# ProPrj__1__2024-10-14.net
KiCad netlist of a schematic drawn in EasyEDA Pro
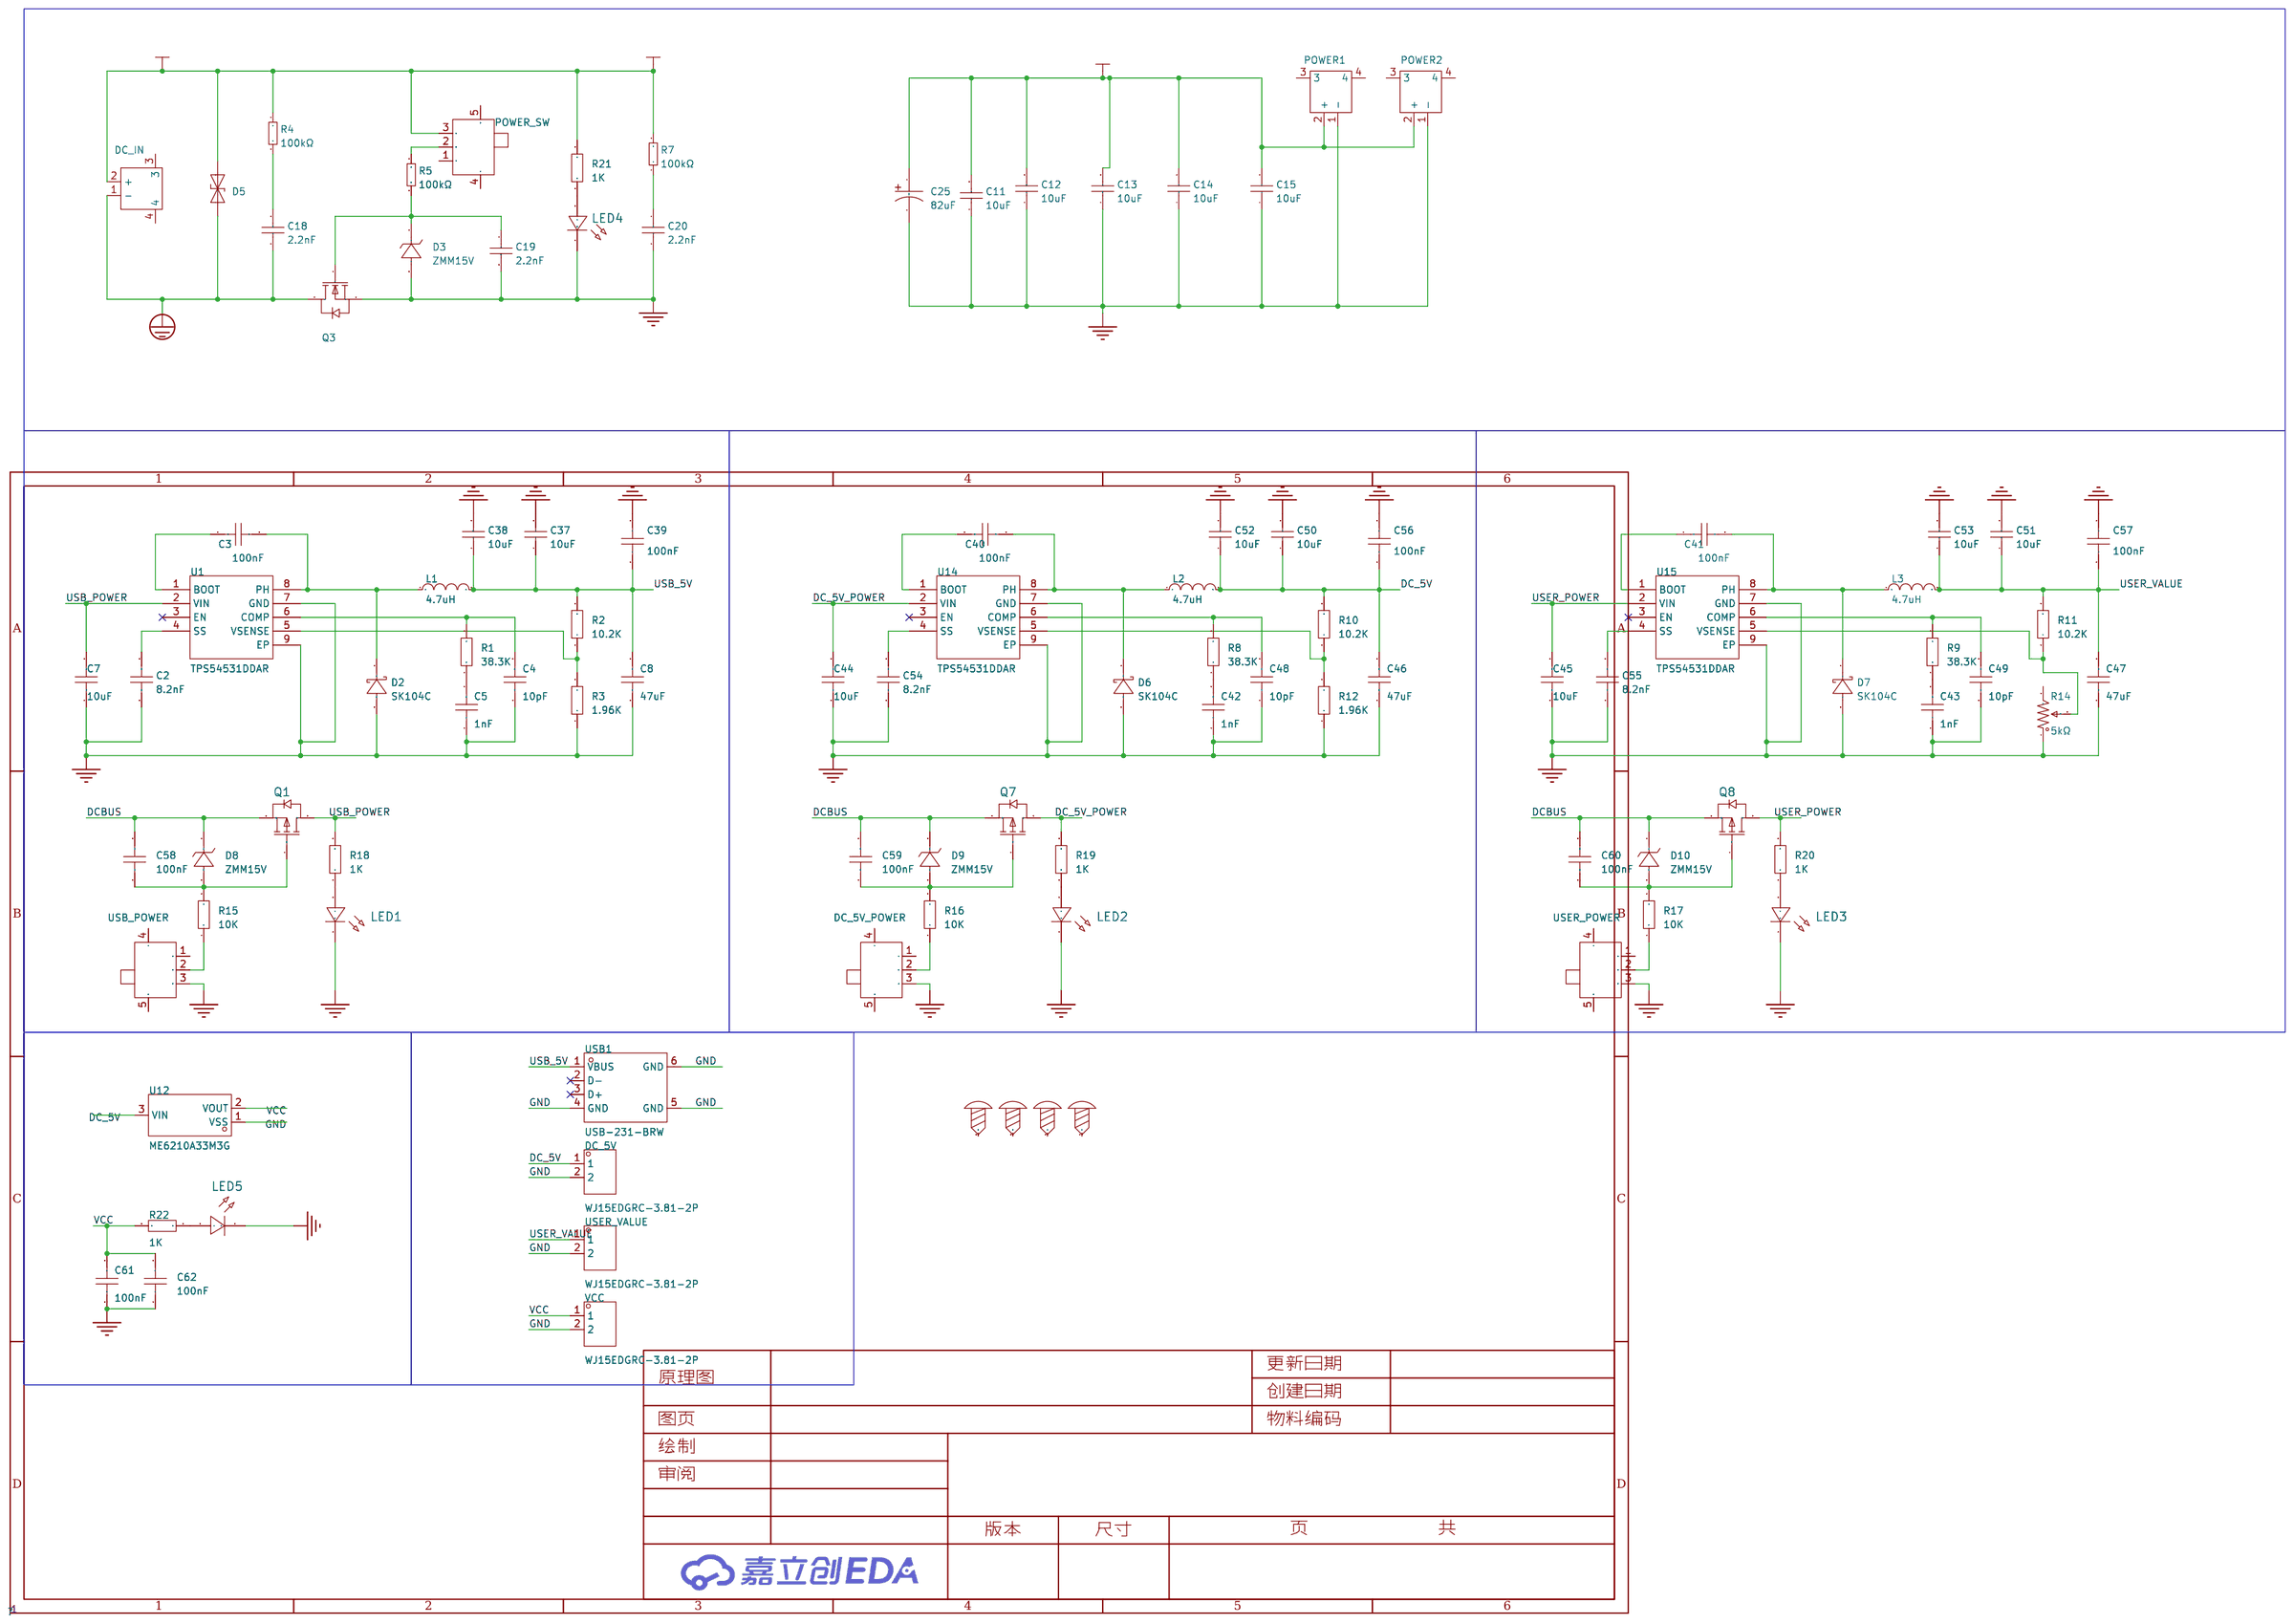
[diagram p0: schematic sheet]

(export (version "E")
  (design (tool "Eeschema 10.0.6"))
  (components
    (comp (ref "C2")
      (value "8.2nF")
      (footprint "easyedapro:C0603")
      (libsource (lib "easyedapro") (part "CapAcitance"))
    )
    (comp (ref "C3")
      (value "100nF")
      (footprint "easyedapro:C0603")
      (libsource (lib "easyedapro") (part "CapAcitance"))
    )
    (comp (ref "C4")
      (value "10pF")
      (footprint "easyedapro:C0603")
      (libsource (lib "easyedapro") (part "CapAcitance"))
    )
    (comp (ref "C5")
      (value "1nF")
      (footprint "easyedapro:C0603")
      (libsource (lib "easyedapro") (part "CapAcitance"))
    )
    (comp (ref "C7")
      (value "10uF")
      (footprint "easyedapro:C1210")
      (description "容值:10uF;精度:±10%;额定电压:50V;材质(温度系数):X7R;")
      (fields
        (field (name "Manufacturer Part") "CL32B106KBJNNNE")
        (field (name "Manufacturer") "SAMSUNG(三星)")
      )
      (libsource (lib "easyedapro") (part "CL32B106KBJNNNE"))
    )
    (comp (ref "C8")
      (value "47uF")
      (footprint "easyedapro:C1210")
      (description "容值:47uF;精度:±10%;额定电压:16V;材质(温度系数):X5R;")
      (fields
        (field (name "Manufacturer Part") "CC1210KKX5R7BB476")
        (field (name "Manufacturer") "YAGEO(国巨)")
      )
      (libsource (lib "easyedapro") (part "CC1210KKX5R7BB476"))
    )
    (comp (ref "C11") (value "10uF") (footprint "easyedapro:C1206_S") (libsource (lib "") (part "C1206_S_1")))
    (comp (ref "C12") (value "10uF") (footprint "easyedapro:C1206_S") (libsource (lib "") (part "C1206_S_1")))
    (comp (ref "C13") (value "10uF") (footprint "easyedapro:C1206_S") (libsource (lib "") (part "C1206_S_1")))
    (comp (ref "C14") (value "10uF") (footprint "easyedapro:C1206_S") (libsource (lib "") (part "C1206_S_1")))
    (comp (ref "C15") (value "10uF") (footprint "easyedapro:C1206_S") (libsource (lib "") (part "C1206_S_1")))
    (comp (ref "C18")
      (value "2.2nF")
      (footprint "easyedapro:C0603_S")
      (fields (field (name "Manufacturer Part") "0603B222K500NT") (field (name "Manufacturer") "FH(风华)"))
      (libsource (lib "easyedapro") (part "C0603_S"))
    )
    (comp (ref "C19")
      (value "2.2nF")
      (footprint "easyedapro:C0603_S")
      (fields (field (name "Manufacturer Part") "0603B222K500NT") (field (name "Manufacturer") "FH(风华)"))
      (libsource (lib "easyedapro") (part "C0603_S"))
    )
    (comp (ref "C20")
      (value "2.2nF")
      (footprint "easyedapro:C0603_S")
      (fields (field (name "Manufacturer Part") "0603B222K500NT") (field (name "Manufacturer") "FH(风华)"))
      (libsource (lib "easyedapro") (part "C0603_S"))
    )
    (comp (ref "C25")
      (value "82uF")
      (footprint "easyedapro:CAP-SMD_BD10.0-L10.3-W10.3-LS11.0-R-RD")
      (description "容值:82uF;精度:±20%;额定电压:80V;纹波电流:668mA@100kHz;等效串联电阻:-;")
      (fields (field (name "Manufacturer Part") "VKME1001K820MV") (field (name "Manufacturer") "Ymin(永铭)"))
      (libsource (lib "easyedapro") (part "VKME1001K820MV"))
    )
    (comp (ref "C37")
      (value "10uF")
      (footprint "easyedapro:C1206_S")
      (libsource (lib "easyedapro") (part "C1206_S"))
    )
    (comp (ref "C38")
      (value "10uF")
      (footprint "easyedapro:C1206_S")
      (libsource (lib "easyedapro") (part "C1206_S"))
    )
    (comp (ref "C39")
      (value "100nF")
      (footprint "easyedapro:C0603")
      (libsource (lib "easyedapro") (part "CapAcitance"))
    )
    (comp (ref "C40")
      (value "100nF")
      (footprint "easyedapro:C0603")
      (libsource (lib "easyedapro") (part "CapAcitance"))
    )
    (comp (ref "C41")
      (value "100nF")
      (footprint "easyedapro:C0603")
      (libsource (lib "easyedapro") (part "CapAcitance"))
    )
    (comp (ref "C42")
      (value "1nF")
      (footprint "easyedapro:C0603")
      (libsource (lib "easyedapro") (part "CapAcitance"))
    )
    (comp (ref "C43")
      (value "1nF")
      (footprint "easyedapro:C0603")
      (libsource (lib "easyedapro") (part "CapAcitance"))
    )
    (comp (ref "C44")
      (value "10uF")
      (footprint "easyedapro:C1210")
      (description "容值:10uF;精度:±10%;额定电压:50V;材质(温度系数):X7R;")
      (fields
        (field (name "Manufacturer Part") "CL32B106KBJNNNE")
        (field (name "Manufacturer") "SAMSUNG(三星)")
      )
      (libsource (lib "easyedapro") (part "CL32B106KBJNNNE"))
    )
    (comp (ref "C45")
      (value "10uF")
      (footprint "easyedapro:C1210")
      (description "容值:10uF;精度:±10%;额定电压:50V;材质(温度系数):X7R;")
      (fields
        (field (name "Manufacturer Part") "CL32B106KBJNNNE")
        (field (name "Manufacturer") "SAMSUNG(三星)")
      )
      (libsource (lib "easyedapro") (part "CL32B106KBJNNNE"))
    )
    (comp (ref "C46")
      (value "47uF")
      (footprint "easyedapro:C1210")
      (description "容值:47uF;精度:±10%;额定电压:16V;材质(温度系数):X5R;")
      (fields
        (field (name "Manufacturer Part") "CC1210KKX5R7BB476")
        (field (name "Manufacturer") "YAGEO(国巨)")
      )
      (libsource (lib "easyedapro") (part "CC1210KKX5R7BB476"))
    )
    (comp (ref "C47")
      (value "47uF")
      (footprint "easyedapro:C1210")
      (description "容值:47uF;精度:±10%;额定电压:16V;材质(温度系数):X5R;")
      (fields
        (field (name "Manufacturer Part") "CC1210KKX5R7BB476")
        (field (name "Manufacturer") "YAGEO(国巨)")
      )
      (libsource (lib "easyedapro") (part "CC1210KKX5R7BB476"))
    )
    (comp (ref "C48")
      (value "10pF")
      (footprint "easyedapro:C0603")
      (libsource (lib "easyedapro") (part "CapAcitance"))
    )
    (comp (ref "C49")
      (value "10pF")
      (footprint "easyedapro:C0603")
      (libsource (lib "easyedapro") (part "CapAcitance"))
    )
    (comp (ref "C50")
      (value "10uF")
      (footprint "easyedapro:C1206_S")
      (libsource (lib "easyedapro") (part "C1206_S"))
    )
    (comp (ref "C51")
      (value "10uF")
      (footprint "easyedapro:C1206_S")
      (libsource (lib "easyedapro") (part "C1206_S"))
    )
    (comp (ref "C52")
      (value "10uF")
      (footprint "easyedapro:C1206_S")
      (libsource (lib "easyedapro") (part "C1206_S"))
    )
    (comp (ref "C53")
      (value "10uF")
      (footprint "easyedapro:C1206_S")
      (libsource (lib "easyedapro") (part "C1206_S"))
    )
    (comp (ref "C54")
      (value "8.2nF")
      (footprint "easyedapro:C0603")
      (libsource (lib "easyedapro") (part "CapAcitance"))
    )
    (comp (ref "C55")
      (value "8.2nF")
      (footprint "easyedapro:C0603")
      (libsource (lib "easyedapro") (part "CapAcitance"))
    )
    (comp (ref "C56")
      (value "100nF")
      (footprint "easyedapro:C0603")
      (libsource (lib "easyedapro") (part "CapAcitance"))
    )
    (comp (ref "C57")
      (value "100nF")
      (footprint "easyedapro:C0603")
      (libsource (lib "easyedapro") (part "CapAcitance"))
    )
    (comp (ref "C58")
      (value "100nF")
      (footprint "easyedapro:C0603")
      (libsource (lib "easyedapro") (part "CapAcitance"))
    )
    (comp (ref "C59")
      (value "100nF")
      (footprint "easyedapro:C0603")
      (libsource (lib "easyedapro") (part "CapAcitance"))
    )
    (comp (ref "C60")
      (value "100nF")
      (footprint "easyedapro:C0603")
      (libsource (lib "easyedapro") (part "CapAcitance"))
    )
    (comp (ref "C61")
      (value "100nF")
      (footprint "easyedapro:C0603")
      (libsource (lib "easyedapro") (part "CapAcitance"))
    )
    (comp (ref "C62")
      (value "100nF")
      (footprint "easyedapro:C0603")
      (libsource (lib "easyedapro") (part "CapAcitance"))
    )
    (comp (ref "D2")
      (value "SK104C")
      (footprint "easyedapro:SMC_L6.9-W5.9-LS7.9-RD")
      (description "二极管配置:独立式;正向压降(Vf):550mV@10A;直流反向耐压(Vr):40V;平均整流电流(Io):10A;")
      (fields (field (name "Manufacturer") "宏迦橙"))
      (libsource (lib "easyedapro") (part "SK104C"))
    )
    (comp (ref "D3")
      (value "ZMM15V")
      (footprint "easyedapro:LL-34_L3.5-W1.5-RD-2")
      (description "二极管配置:独立式;稳压值(标称值):15V;稳压值(范围):13.8V~15.6V;精度:±5%;功率:500mW;阻抗(Zzt):30Ω;")
      (fields (field (name "Manufacturer") "YONGYUTAI(永裕泰)"))
      (libsource (lib "easyedapro") (part "ZMM15V"))
    )
    (comp (ref "D5")
      (value "1.5SMC30CAHE3/57T")
      (footprint "easyedapro:SMC_L6.8-W5.9-LS7.8-BI")
      (fields (field (name "Manufacturer") "VISHAY(威世)"))
      (libsource (lib "easyedapro") (part "1.5SMC30CAHE3/57T"))
    )
    (comp (ref "D6")
      (value "SK104C")
      (footprint "easyedapro:SMC_L6.9-W5.9-LS7.9-RD")
      (description "二极管配置:独立式;正向压降(Vf):550mV@10A;直流反向耐压(Vr):40V;平均整流电流(Io):10A;")
      (fields (field (name "Manufacturer") "宏迦橙"))
      (libsource (lib "easyedapro") (part "SK104C"))
    )
    (comp (ref "D7")
      (value "SK104C")
      (footprint "easyedapro:SMC_L6.9-W5.9-LS7.9-RD")
      (description "二极管配置:独立式;正向压降(Vf):550mV@10A;直流反向耐压(Vr):40V;平均整流电流(Io):10A;")
      (fields (field (name "Manufacturer") "宏迦橙"))
      (libsource (lib "easyedapro") (part "SK104C"))
    )
    (comp (ref "D8")
      (value "ZMM15V")
      (footprint "easyedapro:LL-34_L3.5-W1.5-RD-2")
      (description "二极管配置:独立式;稳压值(标称值):15V;稳压值(范围):13.8V~15.6V;精度:±5%;功率:500mW;阻抗(Zzt):30Ω;")
      (fields (field (name "Manufacturer") "YONGYUTAI(永裕泰)"))
      (libsource (lib "easyedapro") (part "ZMM15V"))
    )
    (comp (ref "D9")
      (value "ZMM15V")
      (footprint "easyedapro:LL-34_L3.5-W1.5-RD-2")
      (description "二极管配置:独立式;稳压值(标称值):15V;稳压值(范围):13.8V~15.6V;精度:±5%;功率:500mW;阻抗(Zzt):30Ω;")
      (fields (field (name "Manufacturer") "YONGYUTAI(永裕泰)"))
      (libsource (lib "easyedapro") (part "ZMM15V"))
    )
    (comp (ref "D10")
      (value "ZMM15V")
      (footprint "easyedapro:LL-34_L3.5-W1.5-RD-2")
      (description "二极管配置:独立式;稳压值(标称值):15V;稳压值(范围):13.8V~15.6V;精度:±5%;功率:500mW;阻抗(Zzt):30Ω;")
      (fields (field (name "Manufacturer") "YONGYUTAI(永裕泰)"))
      (libsource (lib "easyedapro") (part "ZMM15V"))
    )
    (comp (ref "DC_5V")
      (value "WJ15EDGRC-3.81-2P")
      (footprint "easyedapro:CONN-TH_2P-P3.81_WJ15EDGRC-3.81-2P")
      (fields (field (name "Manufacturer") "KANGNEX(康奈克斯电气)"))
      (libsource (lib "easyedapro") (part "WJ15EDGRC-3.81-2P"))
    )
    (comp (ref "DC_5V_POWER")
      (value "SS12D07VG4 087")
      (footprint "easyedapro:SW-TH_SS12D07VG4")
      (description "电路结构:单刀双掷;安装方式:直插;开关颜色:-;额定电流(DC):500mA;额定电压(DC):50V;额定电流(AC):-;额定电压(AC):-;机械寿命:5千次;")
      (fields (field (name "Manufacturer") "SHOU HAN(首韩)"))
      (libsource (lib "easyedapro") (part "SS12D07VG4 087"))
    )
    (comp (ref "DC_IN")
      (value "XT30PW-M30.G.Y")
      (footprint "easyedapro:CONN-TH_XT30PW-M")
      (description "类别:-;类型1:-;")
      (fields (field (name "Manufacturer") "AMASS(艾迈斯)"))
      (libsource (lib "easyedapro") (part "xt30pw-m"))
    )
    (comp (ref "L1")
      (value "4.7uH")
      (footprint "easyedapro:IND-SMD_L7.3-W6.6_MHCI06030")
      (description "电感值:4.7uH;精度:±20%;额定电流:-;饱和电流(Isat):6.55A;类型:一体成型电感;")
      (fields (field (name "Manufacturer Part") "SMMS0630-4R7M") (field (name "Manufacturer") "SXN(顺翔诺)"))
      (libsource (lib "easyedapro") (part "SMMS0630-4R7M"))
    )
    (comp (ref "L2")
      (value "4.7uH")
      (footprint "easyedapro:IND-SMD_L7.3-W6.6_MHCI06030")
      (description "电感值:4.7uH;精度:±20%;额定电流:-;饱和电流(Isat):6.55A;类型:一体成型电感;")
      (fields (field (name "Manufacturer Part") "SMMS0630-4R7M") (field (name "Manufacturer") "SXN(顺翔诺)"))
      (libsource (lib "easyedapro") (part "SMMS0630-4R7M"))
    )
    (comp (ref "L3")
      (value "4.7uH")
      (footprint "easyedapro:IND-SMD_L7.3-W6.6_MHCI06030")
      (description "电感值:4.7uH;精度:±20%;额定电流:-;饱和电流(Isat):6.55A;类型:一体成型电感;")
      (fields (field (name "Manufacturer Part") "SMMS0630-4R7M") (field (name "Manufacturer") "SXN(顺翔诺)"))
      (libsource (lib "easyedapro") (part "SMMS0630-4R7M"))
    )
    (comp (ref "LED1")
      (value "~")
      (footprint "easyedapro:LED_0603")
      (libsource (lib "easyedapro") (part "LED_R"))
    )
    (comp (ref "LED2")
      (value "~")
      (footprint "easyedapro:LED_0603")
      (libsource (lib "easyedapro") (part "LED_R"))
    )
    (comp (ref "LED3")
      (value "~")
      (footprint "easyedapro:LED_0603")
      (libsource (lib "easyedapro") (part "LED_R"))
    )
    (comp (ref "LED4")
      (value "~")
      (footprint "easyedapro:LED_0603")
      (libsource (lib "easyedapro") (part "LED_R"))
    )
    (comp (ref "LED5")
      (value "~")
      (footprint "easyedapro:LED_0603")
      (libsource (lib "easyedapro") (part "LED_R"))
    )
    (comp (ref "POWER1")
      (value "XT30PW-M30.G.Y")
      (footprint "easyedapro:CONN-TH_XT30PW-M")
      (description "类别:-;类型1:-;")
      (fields (field (name "Manufacturer") "AMASS(艾迈斯)"))
      (libsource (lib "easyedapro") (part "xt30pw-m"))
    )
    (comp (ref "POWER2")
      (value "XT30PW-M30.G.Y")
      (footprint "easyedapro:CONN-TH_XT30PW-M")
      (description "类别:-;类型1:-;")
      (fields (field (name "Manufacturer") "AMASS(艾迈斯)"))
      (libsource (lib "easyedapro") (part "xt30pw-m"))
    )
    (comp (ref "POWER_SW")
      (value "SS12D07VG4 087")
      (footprint "easyedapro:SW-TH_SS12D07VG4")
      (description "电路结构:单刀双掷;安装方式:直插;开关颜色:-;额定电流(DC):500mA;额定电压(DC):50V;额定电流(AC):-;额定电压(AC):-;机械寿命:5千次;")
      (fields (field (name "Manufacturer") "SHOU HAN(首韩)"))
      (libsource (lib "easyedapro") (part "SS12D07VG4 087"))
    )
    (comp (ref "Q1")
      (value "WSD90P06DN56")
      (footprint "easyedapro:N3_PDFN-8_L4.9-W5.8-P1.27-LS6.1-BL")
      (fields (field (name "Manufacturer") "WinsokSemicon"))
      (libsource (lib "easyedapro") (part "WSD90P06DN56"))
    )
    (comp (ref "Q3")
      (value "WSD80120DN56")
      (fields (field (name "Manufacturer") "WINSOK(微硕)"))
      (libsource (lib "easyedapro") (part "WSD80120DN56"))
    )
    (comp (ref "Q7")
      (value "WSD90P06DN56")
      (footprint "easyedapro:N3_PDFN-8_L4.9-W5.8-P1.27-LS6.1-BL")
      (fields (field (name "Manufacturer") "WinsokSemicon"))
      (libsource (lib "easyedapro") (part "WSD90P06DN56"))
    )
    (comp (ref "Q8")
      (value "WSD90P06DN56")
      (footprint "easyedapro:N3_PDFN-8_L4.9-W5.8-P1.27-LS6.1-BL")
      (fields (field (name "Manufacturer") "WinsokSemicon"))
      (libsource (lib "easyedapro") (part "WSD90P06DN56"))
    )
    (comp (ref "R1")
      (value "38.3K")
      (footprint "easyedapro:R0603")
      (libsource (lib "easyedapro") (part "电阻"))
    )
    (comp (ref "R2")
      (value "10.2K")
      (footprint "easyedapro:R0603")
      (libsource (lib "easyedapro") (part "电阻"))
    )
    (comp (ref "R3")
      (value "1.96K")
      (footprint "easyedapro:R0603")
      (libsource (lib "easyedapro") (part "电阻"))
    )
    (comp (ref "R4")
      (value "100kΩ")
      (footprint "easyedapro:R0603_S")
      (fields (field (name "Manufacturer Part") "RC0603FR-07100KL") (field (name "Manufacturer") "YAGEO(国巨)"))
      (libsource (lib "easyedapro") (part "R0603_S"))
    )
    (comp (ref "R5")
      (value "100kΩ")
      (footprint "easyedapro:R0603_S")
      (fields (field (name "Manufacturer Part") "RC0603FR-07100KL") (field (name "Manufacturer") "YAGEO(国巨)"))
      (libsource (lib "easyedapro") (part "R0603_S"))
    )
    (comp (ref "R7")
      (value "100kΩ")
      (footprint "easyedapro:R0603_S")
      (fields (field (name "Manufacturer Part") "RC0603FR-07100KL") (field (name "Manufacturer") "YAGEO(国巨)"))
      (libsource (lib "easyedapro") (part "R0603_S"))
    )
    (comp (ref "R8")
      (value "38.3K")
      (footprint "easyedapro:R0603")
      (libsource (lib "easyedapro") (part "电阻"))
    )
    (comp (ref "R9")
      (value "38.3K")
      (footprint "easyedapro:R0603")
      (libsource (lib "easyedapro") (part "电阻"))
    )
    (comp (ref "R10")
      (value "10.2K")
      (footprint "easyedapro:R0603")
      (libsource (lib "easyedapro") (part "电阻"))
    )
    (comp (ref "R11")
      (value "10.2K")
      (footprint "easyedapro:R0603")
      (libsource (lib "easyedapro") (part "电阻"))
    )
    (comp (ref "R12")
      (value "1.96K")
      (footprint "easyedapro:R0603")
      (libsource (lib "easyedapro") (part "电阻"))
    )
    (comp (ref "R14")
      (value "5kΩ")
      (footprint "easyedapro:RES-ADJ-TH_3362P")
      (description "阻值:5kΩ;精度:±10%;")
      (fields (field (name "Manufacturer Part") "3362P-1-502") (field (name "Manufacturer") "BOCHEN(博晨)"))
      (libsource (lib "easyedapro") (part "3362P-1-502"))
    )
    (comp (ref "R15") (value "10K") (footprint "easyedapro:R0603") (libsource (lib "easyedapro") (part "电阻")))
    (comp (ref "R16") (value "10K") (footprint "easyedapro:R0603") (libsource (lib "easyedapro") (part "电阻")))
    (comp (ref "R17") (value "10K") (footprint "easyedapro:R0603") (libsource (lib "easyedapro") (part "电阻")))
    (comp (ref "R18") (value "1K") (footprint "easyedapro:R0603") (libsource (lib "easyedapro") (part "电阻")))
    (comp (ref "R19") (value "1K") (footprint "easyedapro:R0603") (libsource (lib "easyedapro") (part "电阻")))
    (comp (ref "R20") (value "1K") (footprint "easyedapro:R0603") (libsource (lib "easyedapro") (part "电阻")))
    (comp (ref "R21") (value "1K") (footprint "easyedapro:R0603") (libsource (lib "easyedapro") (part "电阻")))
    (comp (ref "R22") (value "1K") (footprint "easyedapro:R0603") (libsource (lib "easyedapro") (part "电阻")))
    (comp (ref "SCREW1")
      (value "~")
      (footprint "easyedapro:M3螺丝")
      (libsource (lib "easyedapro") (part "螺丝孔"))
    )
    (comp (ref "SCREW2")
      (value "~")
      (footprint "easyedapro:M3螺丝")
      (libsource (lib "easyedapro") (part "螺丝孔"))
    )
    (comp (ref "SCREW3")
      (value "~")
      (footprint "easyedapro:M3螺丝")
      (libsource (lib "easyedapro") (part "螺丝孔"))
    )
    (comp (ref "SCREW4")
      (value "~")
      (footprint "easyedapro:M3螺丝")
      (libsource (lib "easyedapro") (part "螺丝孔"))
    )
    (comp (ref "U1")
      (value "TPS54531DDAR")
      (footprint "easyedapro:SOIC-8_L5.0-W4.0-P1.27-LS6.0-BL-EP2.0")
      (description "功能类型:降压型;输出类型:可调;输入电压:3.5V~28V;输出电压:800mV~26.04V;输出电流(最大值):5A;")
      (fields (field (name "Manufacturer") "TI(德州仪器)"))
      (libsource (lib "easyedapro") (part "TPS54531DDAR"))
    )
    (comp (ref "U12")
      (value "ME6210A33M3G")
      (footprint "easyedapro:SOT-23-3_L3.0-W1.7-P0.95-LS2.9-BR")
      (description "输出类型:固定;最大输入电压:18V;输出电压:3.3V;最大输出电流:500mA;电源纹波抑制比(PSRR):-;输出极性:正极;")
      (fields (field (name "Manufacturer") "MICRONE(南京微盟)"))
      (libsource (lib "easyedapro") (part "ME6210A33M3G"))
    )
    (comp (ref "U14")
      (value "TPS54531DDAR")
      (footprint "easyedapro:SOIC-8_L5.0-W4.0-P1.27-LS6.0-BL-EP2.0")
      (description "功能类型:降压型;输出类型:可调;输入电压:3.5V~28V;输出电压:800mV~26.04V;输出电流(最大值):5A;")
      (fields (field (name "Manufacturer") "TI(德州仪器)"))
      (libsource (lib "easyedapro") (part "TPS54531DDAR"))
    )
    (comp (ref "U15")
      (value "TPS54531DDAR")
      (footprint "easyedapro:SOIC-8_L5.0-W4.0-P1.27-LS6.0-BL-EP2.0")
      (description "功能类型:降压型;输出类型:可调;输入电压:3.5V~28V;输出电压:800mV~26.04V;输出电流(最大值):5A;")
      (fields (field (name "Manufacturer") "TI(德州仪器)"))
      (libsource (lib "easyedapro") (part "TPS54531DDAR"))
    )
    (comp (ref "USB1")
      (value "USB-231-BRW")
      (footprint "easyedapro:USB-A-TH_USB-231-ARY")
      (fields (field (name "Manufacturer") "XUNPU(讯普)"))
      (libsource (lib "easyedapro") (part "USB-231-BRW"))
    )
    (comp (ref "USB_POWER")
      (value "SS12D07VG4 087")
      (footprint "easyedapro:SW-TH_SS12D07VG4")
      (description "电路结构:单刀双掷;安装方式:直插;开关颜色:-;额定电流(DC):500mA;额定电压(DC):50V;额定电流(AC):-;额定电压(AC):-;机械寿命:5千次;")
      (fields (field (name "Manufacturer") "SHOU HAN(首韩)"))
      (libsource (lib "easyedapro") (part "SS12D07VG4 087"))
    )
    (comp (ref "USER_POWER")
      (value "SS12D07VG4 087")
      (footprint "easyedapro:SW-TH_SS12D07VG4")
      (description "电路结构:单刀双掷;安装方式:直插;开关颜色:-;额定电流(DC):500mA;额定电压(DC):50V;额定电流(AC):-;额定电压(AC):-;机械寿命:5千次;")
      (fields (field (name "Manufacturer") "SHOU HAN(首韩)"))
      (libsource (lib "easyedapro") (part "SS12D07VG4 087"))
    )
    (comp (ref "USER_VALUE")
      (value "WJ15EDGRC-3.81-2P")
      (footprint "easyedapro:CONN-TH_2P-P3.81_WJ15EDGRC-3.81-2P")
      (fields (field (name "Manufacturer") "KANGNEX(康奈克斯电气)"))
      (libsource (lib "easyedapro") (part "WJ15EDGRC-3.81-2P"))
    )
    (comp (ref "VCC")
      (value "WJ15EDGRC-3.81-2P")
      (footprint "easyedapro:CONN-TH_2P-P3.81_WJ15EDGRC-3.81-2P")
      (fields (field (name "Manufacturer") "KANGNEX(康奈克斯电气)"))
      (libsource (lib "easyedapro") (part "WJ15EDGRC-3.81-2P"))
    )
  )
  (nets
    (net (code "1") (name "/DC_5V") (class "Default")
      (node (ref "C46") (pin "2") (pinfunction "2_2") (pintype "unspecified"))
      (node (ref "C50") (pin "1") (pinfunction "1_1") (pintype "input"))
      (node (ref "C52") (pin "1") (pinfunction "1_1") (pintype "input"))
      (node (ref "C56") (pin "1") (pinfunction "1_1") (pintype "input"))
      (node (ref "DC_5V") (pin "1") (pinfunction "1_1") (pintype "unspecified"))
      (node (ref "L2") (pin "2") (pinfunction "2_2") (pintype "unspecified"))
      (node (ref "R10") (pin "2") (pinfunction "2_2") (pintype "input"))
      (node (ref "U12") (pin "3") (pinfunction "VIN_3") (pintype "input"))
    )
    (net (code "2") (name "/DC_5V_POWER") (class "Default")
      (node (ref "C44") (pin "2") (pinfunction "2_2") (pintype "unspecified"))
      (node (ref "Q7") (pin "2") (pinfunction "D_2") (pintype "input"))
      (node (ref "R19") (pin "2") (pinfunction "2_2") (pintype "input"))
      (node (ref "U14") (pin "2") (pinfunction "VIN_2") (pintype "unspecified"))
    )
    (net (code "3") (name "/USB_5V") (class "Default")
      (node (ref "C37") (pin "1") (pinfunction "1_1") (pintype "input"))
      (node (ref "C38") (pin "1") (pinfunction "1_1") (pintype "input"))
      (node (ref "C39") (pin "1") (pinfunction "1_1") (pintype "input"))
      (node (ref "C8") (pin "2") (pinfunction "2_2") (pintype "unspecified"))
      (node (ref "L1") (pin "2") (pinfunction "2_2") (pintype "unspecified"))
      (node (ref "R2") (pin "2") (pinfunction "2_2") (pintype "input"))
      (node (ref "USB1") (pin "1") (pinfunction "VBUS_1") (pintype "unspecified"))
    )
    (net (code "4") (name "/USB_POWER") (class "Default")
      (node (ref "C7") (pin "2") (pinfunction "2_2") (pintype "unspecified"))
      (node (ref "Q1") (pin "2") (pinfunction "D_2") (pintype "input"))
      (node (ref "R18") (pin "2") (pinfunction "2_2") (pintype "input"))
      (node (ref "U1") (pin "2") (pinfunction "VIN_2") (pintype "unspecified"))
    )
    (net (code "5") (name "/USER_POWER") (class "Default")
      (node (ref "C45") (pin "2") (pinfunction "2_2") (pintype "unspecified"))
      (node (ref "Q8") (pin "2") (pinfunction "D_2") (pintype "input"))
      (node (ref "R20") (pin "2") (pinfunction "2_2") (pintype "input"))
      (node (ref "U15") (pin "2") (pinfunction "VIN_2") (pintype "unspecified"))
    )
    (net (code "6") (name "/USER_VALUE") (class "Default")
      (node (ref "C47") (pin "2") (pinfunction "2_2") (pintype "unspecified"))
      (node (ref "C51") (pin "1") (pinfunction "1_1") (pintype "input"))
      (node (ref "C53") (pin "1") (pinfunction "1_1") (pintype "input"))
      (node (ref "C57") (pin "1") (pinfunction "1_1") (pintype "input"))
      (node (ref "L3") (pin "2") (pinfunction "2_2") (pintype "unspecified"))
      (node (ref "R11") (pin "2") (pinfunction "2_2") (pintype "input"))
      (node (ref "USER_VALUE") (pin "1") (pinfunction "1_1") (pintype "unspecified"))
    )
    (net (code "7") (name "/VCC") (class "Default")
      (node (ref "C61") (pin "2") (pinfunction "2_2") (pintype "input"))
      (node (ref "C62") (pin "2") (pinfunction "2_2") (pintype "input"))
      (node (ref "R22") (pin "2") (pinfunction "2_2") (pintype "input"))
      (node (ref "U12") (pin "2") (pinfunction "VOUT_2") (pintype "input"))
      (node (ref "VCC") (pin "1") (pinfunction "1_1") (pintype "unspecified"))
    )
    (net (code "8") (name "DCBUS") (class "Default")
      (node (ref "C11") (pin "2") (pinfunction "2_2") (pintype "input"))
      (node (ref "C12") (pin "2") (pinfunction "2_2") (pintype "input"))
      (node (ref "C13") (pin "2") (pinfunction "2_2") (pintype "input"))
      (node (ref "C14") (pin "2") (pinfunction "2_2") (pintype "input"))
      (node (ref "C15") (pin "2") (pinfunction "2_2") (pintype "input"))
      (node (ref "C25") (pin "1") (pinfunction "1_1") (pintype "input"))
      (node (ref "C58") (pin "2") (pinfunction "2_2") (pintype "input"))
      (node (ref "C59") (pin "2") (pinfunction "2_2") (pintype "input"))
      (node (ref "C60") (pin "2") (pinfunction "2_2") (pintype "input"))
      (node (ref "D10") (pin "1") (pinfunction "K_1") (pintype "unspecified"))
      (node (ref "D5") (pin "2") (pinfunction "A_2") (pintype "input"))
      (node (ref "D8") (pin "1") (pinfunction "K_1") (pintype "unspecified"))
      (node (ref "D9") (pin "1") (pinfunction "K_1") (pintype "unspecified"))
      (node (ref "DC_IN") (pin "2") (pinfunction "+_2") (pintype "unspecified"))
      (node (ref "POWER1") (pin "2") (pinfunction "+_2") (pintype "unspecified"))
      (node (ref "POWER2") (pin "2") (pinfunction "+_2") (pintype "unspecified"))
      (node (ref "POWER_SW") (pin "3") (pinfunction "3_3") (pintype "unspecified"))
      (node (ref "Q1") (pin "3") (pinfunction "S_3") (pintype "input"))
      (node (ref "Q7") (pin "3") (pinfunction "S_3") (pintype "input"))
      (node (ref "Q8") (pin "3") (pinfunction "S_3") (pintype "input"))
      (node (ref "R21") (pin "2") (pinfunction "2_2") (pintype "input"))
      (node (ref "R4") (pin "2") (pinfunction "2_2") (pintype "input"))
      (node (ref "R7") (pin "2") (pinfunction "2_2") (pintype "input"))
    )
    (net (code "9") (name "GND") (class "Default")
      (node (ref "C11") (pin "1") (pinfunction "1_1") (pintype "input"))
      (node (ref "C12") (pin "1") (pinfunction "1_1") (pintype "input"))
      (node (ref "C13") (pin "1") (pinfunction "1_1") (pintype "input"))
      (node (ref "C14") (pin "1") (pinfunction "1_1") (pintype "input"))
      (node (ref "C15") (pin "1") (pinfunction "1_1") (pintype "input"))
      (node (ref "C19") (pin "2") (pinfunction "2_2") (pintype "input"))
      (node (ref "C2") (pin "1") (pinfunction "1_1") (pintype "input"))
      (node (ref "C20") (pin "2") (pinfunction "2_2") (pintype "input"))
      (node (ref "C25") (pin "2") (pinfunction "2_2") (pintype "input"))
      (node (ref "C37") (pin "2") (pinfunction "2_2") (pintype "input"))
      (node (ref "C38") (pin "2") (pinfunction "2_2") (pintype "input"))
      (node (ref "C39") (pin "2") (pinfunction "2_2") (pintype "input"))
      (node (ref "C4") (pin "1") (pinfunction "1_1") (pintype "input"))
      (node (ref "C42") (pin "1") (pinfunction "1_1") (pintype "input"))
      (node (ref "C43") (pin "1") (pinfunction "1_1") (pintype "input"))
      (node (ref "C44") (pin "1") (pinfunction "1_1") (pintype "unspecified"))
      (node (ref "C45") (pin "1") (pinfunction "1_1") (pintype "unspecified"))
      (node (ref "C46") (pin "1") (pinfunction "1_1") (pintype "unspecified"))
      (node (ref "C47") (pin "1") (pinfunction "1_1") (pintype "unspecified"))
      (node (ref "C48") (pin "1") (pinfunction "1_1") (pintype "input"))
      (node (ref "C49") (pin "1") (pinfunction "1_1") (pintype "input"))
      (node (ref "C5") (pin "1") (pinfunction "1_1") (pintype "input"))
      (node (ref "C50") (pin "2") (pinfunction "2_2") (pintype "input"))
      (node (ref "C51") (pin "2") (pinfunction "2_2") (pintype "input"))
      (node (ref "C52") (pin "2") (pinfunction "2_2") (pintype "input"))
      (node (ref "C53") (pin "2") (pinfunction "2_2") (pintype "input"))
      (node (ref "C54") (pin "1") (pinfunction "1_1") (pintype "input"))
      (node (ref "C55") (pin "1") (pinfunction "1_1") (pintype "input"))
      (node (ref "C56") (pin "2") (pinfunction "2_2") (pintype "input"))
      (node (ref "C57") (pin "2") (pinfunction "2_2") (pintype "input"))
      (node (ref "C61") (pin "1") (pinfunction "1_1") (pintype "input"))
      (node (ref "C62") (pin "1") (pinfunction "1_1") (pintype "input"))
      (node (ref "C7") (pin "1") (pinfunction "1_1") (pintype "unspecified"))
      (node (ref "C8") (pin "1") (pinfunction "1_1") (pintype "unspecified"))
      (node (ref "D2") (pin "2") (pinfunction "A_2") (pintype "unspecified"))
      (node (ref "D3") (pin "2") (pinfunction "A_2") (pintype "unspecified"))
      (node (ref "D6") (pin "2") (pinfunction "A_2") (pintype "unspecified"))
      (node (ref "D7") (pin "2") (pinfunction "A_2") (pintype "unspecified"))
      (node (ref "DC_5V") (pin "2") (pinfunction "2_2") (pintype "unspecified"))
      (node (ref "DC_5V_POWER") (pin "3") (pinfunction "3_3") (pintype "unspecified"))
      (node (ref "LED1") (pin "1") (pinfunction "C_1") (pintype "input"))
      (node (ref "LED2") (pin "1") (pinfunction "C_1") (pintype "input"))
      (node (ref "LED3") (pin "1") (pinfunction "C_1") (pintype "input"))
      (node (ref "LED4") (pin "1") (pinfunction "C_1") (pintype "input"))
      (node (ref "LED5") (pin "1") (pinfunction "C_1") (pintype "input"))
      (node (ref "POWER1") (pin "1") (pinfunction "-_1") (pintype "unspecified"))
      (node (ref "POWER2") (pin "1") (pinfunction "-_1") (pintype "unspecified"))
      (node (ref "Q3") (pin "3") (pinfunction "S_3") (pintype "unspecified"))
      (node (ref "R12") (pin "1") (pinfunction "1_1") (pintype "input"))
      (node (ref "R14") (pin "1") (pinfunction "1_1") (pintype "unspecified"))
      (node (ref "R3") (pin "1") (pinfunction "1_1") (pintype "input"))
      (node (ref "U1") (pin "7") (pinfunction "GND_7") (pintype "unspecified"))
      (node (ref "U1") (pin "9") (pinfunction "EP_9") (pintype "unspecified"))
      (node (ref "U12") (pin "1") (pinfunction "VSS_1") (pintype "input"))
      (node (ref "U14") (pin "7") (pinfunction "GND_7") (pintype "unspecified"))
      (node (ref "U14") (pin "9") (pinfunction "EP_9") (pintype "unspecified"))
      (node (ref "U15") (pin "7") (pinfunction "GND_7") (pintype "unspecified"))
      (node (ref "U15") (pin "9") (pinfunction "EP_9") (pintype "unspecified"))
      (node (ref "USB1") (pin "4") (pinfunction "GND_4") (pintype "unspecified"))
      (node (ref "USB1") (pin "5") (pinfunction "GND_5") (pintype "unspecified"))
      (node (ref "USB1") (pin "6") (pinfunction "GND_6") (pintype "unspecified"))
      (node (ref "USB_POWER") (pin "3") (pinfunction "3_3") (pintype "unspecified"))
      (node (ref "USER_POWER") (pin "3") (pinfunction "3_3") (pintype "unspecified"))
      (node (ref "USER_VALUE") (pin "2") (pinfunction "2_2") (pintype "unspecified"))
      (node (ref "VCC") (pin "2") (pinfunction "2_2") (pintype "unspecified"))
    )
    (net (code "10") (name "Net-(C5-Pad2)") (class "Default")
      (node (ref "C5") (pin "2") (pinfunction "2_2") (pintype "input"))
      (node (ref "R1") (pin "1") (pinfunction "1_1") (pintype "input"))
    )
    (net (code "11") (name "Net-(C18-Pad1)") (class "Default")
      (node (ref "C18") (pin "1") (pinfunction "1_1") (pintype "input"))
      (node (ref "R4") (pin "1") (pinfunction "1_1") (pintype "input"))
    )
    (net (code "12") (name "Net-(C20-Pad1)") (class "Default")
      (node (ref "C20") (pin "1") (pinfunction "1_1") (pintype "input"))
      (node (ref "R7") (pin "1") (pinfunction "1_1") (pintype "input"))
    )
    (net (code "13") (name "Net-(C42-Pad2)") (class "Default")
      (node (ref "C42") (pin "2") (pinfunction "2_2") (pintype "input"))
      (node (ref "R8") (pin "1") (pinfunction "1_1") (pintype "input"))
    )
    (net (code "14") (name "Net-(C43-Pad2)") (class "Default")
      (node (ref "C43") (pin "2") (pinfunction "2_2") (pintype "input"))
      (node (ref "R9") (pin "1") (pinfunction "1_1") (pintype "input"))
    )
    (net (code "15") (name "Net-(D2-K)") (class "Default")
      (node (ref "C3") (pin "2") (pinfunction "2_2") (pintype "input"))
      (node (ref "D2") (pin "1") (pinfunction "K_1") (pintype "unspecified"))
      (node (ref "L1") (pin "1") (pinfunction "1_1") (pintype "unspecified"))
      (node (ref "U1") (pin "8") (pinfunction "PH_8") (pintype "unspecified"))
    )
    (net (code "16") (name "Net-(D3-K)") (class "Default")
      (node (ref "C19") (pin "1") (pinfunction "1_1") (pintype "input"))
      (node (ref "D3") (pin "1") (pinfunction "K_1") (pintype "unspecified"))
      (node (ref "Q3") (pin "1") (pinfunction "G_1") (pintype "unspecified"))
      (node (ref "R5") (pin "1") (pinfunction "1_1") (pintype "input"))
    )
    (net (code "17") (name "Net-(D6-K)") (class "Default")
      (node (ref "C40") (pin "2") (pinfunction "2_2") (pintype "input"))
      (node (ref "D6") (pin "1") (pinfunction "K_1") (pintype "unspecified"))
      (node (ref "L2") (pin "1") (pinfunction "1_1") (pintype "unspecified"))
      (node (ref "U14") (pin "8") (pinfunction "PH_8") (pintype "unspecified"))
    )
    (net (code "18") (name "Net-(D7-K)") (class "Default")
      (node (ref "C41") (pin "2") (pinfunction "2_2") (pintype "input"))
      (node (ref "D7") (pin "1") (pinfunction "K_1") (pintype "unspecified"))
      (node (ref "L3") (pin "1") (pinfunction "1_1") (pintype "unspecified"))
      (node (ref "U15") (pin "8") (pinfunction "PH_8") (pintype "unspecified"))
    )
    (net (code "19") (name "Net-(D8-A)") (class "Default")
      (node (ref "C58") (pin "1") (pinfunction "1_1") (pintype "input"))
      (node (ref "D8") (pin "2") (pinfunction "A_2") (pintype "unspecified"))
      (node (ref "Q1") (pin "1") (pinfunction "G_1") (pintype "input"))
      (node (ref "R15") (pin "2") (pinfunction "2_2") (pintype "input"))
    )
    (net (code "20") (name "Net-(D9-A)") (class "Default")
      (node (ref "C59") (pin "1") (pinfunction "1_1") (pintype "input"))
      (node (ref "D9") (pin "2") (pinfunction "A_2") (pintype "unspecified"))
      (node (ref "Q7") (pin "1") (pinfunction "G_1") (pintype "input"))
      (node (ref "R16") (pin "2") (pinfunction "2_2") (pintype "input"))
    )
    (net (code "21") (name "Net-(D10-A)") (class "Default")
      (node (ref "C60") (pin "1") (pinfunction "1_1") (pintype "input"))
      (node (ref "D10") (pin "2") (pinfunction "A_2") (pintype "unspecified"))
      (node (ref "Q8") (pin "1") (pinfunction "G_1") (pintype "input"))
      (node (ref "R17") (pin "2") (pinfunction "2_2") (pintype "input"))
    )
    (net (code "22") (name "Net-(DC_5V_POWER-Pad2)") (class "Default")
      (node (ref "DC_5V_POWER") (pin "2") (pinfunction "2_2") (pintype "unspecified"))
      (node (ref "R16") (pin "1") (pinfunction "1_1") (pintype "input"))
    )
    (net (code "23") (name "Net-(LED1-A)") (class "Default")
      (node (ref "LED1") (pin "2") (pinfunction "A_2") (pintype "input"))
      (node (ref "R18") (pin "1") (pinfunction "1_1") (pintype "input"))
    )
    (net (code "24") (name "Net-(LED2-A)") (class "Default")
      (node (ref "LED2") (pin "2") (pinfunction "A_2") (pintype "input"))
      (node (ref "R19") (pin "1") (pinfunction "1_1") (pintype "input"))
    )
    (net (code "25") (name "Net-(LED3-A)") (class "Default")
      (node (ref "LED3") (pin "2") (pinfunction "A_2") (pintype "input"))
      (node (ref "R20") (pin "1") (pinfunction "1_1") (pintype "input"))
    )
    (net (code "26") (name "Net-(LED4-A)") (class "Default")
      (node (ref "LED4") (pin "2") (pinfunction "A_2") (pintype "input"))
      (node (ref "R21") (pin "1") (pinfunction "1_1") (pintype "input"))
    )
    (net (code "27") (name "Net-(LED5-A)") (class "Default")
      (node (ref "LED5") (pin "2") (pinfunction "A_2") (pintype "input"))
      (node (ref "R22") (pin "1") (pinfunction "1_1") (pintype "input"))
    )
    (net (code "28") (name "Net-(POWER_SW-Pad2)") (class "Default")
      (node (ref "POWER_SW") (pin "2") (pinfunction "2_2") (pintype "unspecified"))
      (node (ref "R5") (pin "2") (pinfunction "2_2") (pintype "input"))
    )
    (net (code "29") (name "Net-(R15-Pad1)") (class "Default")
      (node (ref "R15") (pin "1") (pinfunction "1_1") (pintype "input"))
      (node (ref "USB_POWER") (pin "2") (pinfunction "2_2") (pintype "unspecified"))
    )
    (net (code "30") (name "Net-(R17-Pad1)") (class "Default")
      (node (ref "R17") (pin "1") (pinfunction "1_1") (pintype "input"))
      (node (ref "USER_POWER") (pin "2") (pinfunction "2_2") (pintype "unspecified"))
    )
    (net (code "31") (name "Net-(U1-BOOT)") (class "Default")
      (node (ref "C3") (pin "1") (pinfunction "1_1") (pintype "input"))
      (node (ref "U1") (pin "1") (pinfunction "BOOT_1") (pintype "unspecified"))
    )
    (net (code "32") (name "Net-(U1-COMP)") (class "Default")
      (node (ref "C4") (pin "2") (pinfunction "2_2") (pintype "input"))
      (node (ref "R1") (pin "2") (pinfunction "2_2") (pintype "input"))
      (node (ref "U1") (pin "6") (pinfunction "COMP_6") (pintype "unspecified"))
    )
    (net (code "33") (name "Net-(U1-SS)") (class "Default")
      (node (ref "C2") (pin "2") (pinfunction "2_2") (pintype "input"))
      (node (ref "U1") (pin "4") (pinfunction "SS_4") (pintype "unspecified"))
    )
    (net (code "34") (name "Net-(U1-VSENSE)") (class "Default")
      (node (ref "R2") (pin "1") (pinfunction "1_1") (pintype "input"))
      (node (ref "R3") (pin "2") (pinfunction "2_2") (pintype "input"))
      (node (ref "U1") (pin "5") (pinfunction "VSENSE_5") (pintype "unspecified"))
    )
    (net (code "35") (name "Net-(U14-BOOT)") (class "Default")
      (node (ref "C40") (pin "1") (pinfunction "1_1") (pintype "input"))
      (node (ref "U14") (pin "1") (pinfunction "BOOT_1") (pintype "unspecified"))
    )
    (net (code "36") (name "Net-(U14-COMP)") (class "Default")
      (node (ref "C48") (pin "2") (pinfunction "2_2") (pintype "input"))
      (node (ref "R8") (pin "2") (pinfunction "2_2") (pintype "input"))
      (node (ref "U14") (pin "6") (pinfunction "COMP_6") (pintype "unspecified"))
    )
    (net (code "37") (name "Net-(U14-SS)") (class "Default")
      (node (ref "C54") (pin "2") (pinfunction "2_2") (pintype "input"))
      (node (ref "U14") (pin "4") (pinfunction "SS_4") (pintype "unspecified"))
    )
    (net (code "38") (name "Net-(U14-VSENSE)") (class "Default")
      (node (ref "R10") (pin "1") (pinfunction "1_1") (pintype "input"))
      (node (ref "R12") (pin "2") (pinfunction "2_2") (pintype "input"))
      (node (ref "U14") (pin "5") (pinfunction "VSENSE_5") (pintype "unspecified"))
    )
    (net (code "39") (name "Net-(U15-BOOT)") (class "Default")
      (node (ref "C41") (pin "1") (pinfunction "1_1") (pintype "input"))
      (node (ref "U15") (pin "1") (pinfunction "BOOT_1") (pintype "unspecified"))
    )
    (net (code "40") (name "Net-(U15-COMP)") (class "Default")
      (node (ref "C49") (pin "2") (pinfunction "2_2") (pintype "input"))
      (node (ref "R9") (pin "2") (pinfunction "2_2") (pintype "input"))
      (node (ref "U15") (pin "6") (pinfunction "COMP_6") (pintype "unspecified"))
    )
    (net (code "41") (name "Net-(U15-SS)") (class "Default")
      (node (ref "C55") (pin "2") (pinfunction "2_2") (pintype "input"))
      (node (ref "U15") (pin "4") (pinfunction "SS_4") (pintype "unspecified"))
    )
    (net (code "42") (name "Net-(U15-VSENSE)") (class "Default")
      (node (ref "R11") (pin "1") (pinfunction "1_1") (pintype "input"))
      (node (ref "R14") (pin "2") (pinfunction "2_2") (pintype "unspecified"))
      (node (ref "U15") (pin "5") (pinfunction "VSENSE_5") (pintype "unspecified"))
    )
    (net (code "43") (name "PGND") (class "Default")
      (node (ref "C18") (pin "2") (pinfunction "2_2") (pintype "input"))
      (node (ref "D5") (pin "1") (pinfunction "K_1") (pintype "input"))
      (node (ref "DC_IN") (pin "1") (pinfunction "-_1") (pintype "unspecified"))
      (node (ref "Q3") (pin "2") (pinfunction "D_2") (pintype "unspecified"))
    )
    (net (code "44") (name "unconnected-(DC_5V_POWER-Pad1)") (class "Default")
      (node (ref "DC_5V_POWER") (pin "1") (pinfunction "1_1") (pintype "unspecified"))
    )
    (net (code "45") (name "unconnected-(DC_5V_POWER-Pad4)") (class "Default")
      (node (ref "DC_5V_POWER") (pin "4") (pinfunction "4_4") (pintype "unspecified"))
    )
    (net (code "46") (name "unconnected-(DC_5V_POWER-Pad5)") (class "Default")
      (node (ref "DC_5V_POWER") (pin "5") (pinfunction "5_5") (pintype "unspecified"))
    )
    (net (code "47") (name "unconnected-(DC_IN-Pad3)") (class "Default")
      (node (ref "DC_IN") (pin "3") (pinfunction "3_3") (pintype "unspecified"))
    )
    (net (code "48") (name "unconnected-(DC_IN-Pad4)") (class "Default")
      (node (ref "DC_IN") (pin "4") (pinfunction "4_4") (pintype "unspecified"))
    )
    (net (code "49") (name "unconnected-(POWER1-Pad3)") (class "Default")
      (node (ref "POWER1") (pin "3") (pinfunction "3_3") (pintype "unspecified"))
    )
    (net (code "50") (name "unconnected-(POWER1-Pad4)") (class "Default")
      (node (ref "POWER1") (pin "4") (pinfunction "4_4") (pintype "unspecified"))
    )
    (net (code "51") (name "unconnected-(POWER2-Pad3)") (class "Default")
      (node (ref "POWER2") (pin "3") (pinfunction "3_3") (pintype "unspecified"))
    )
    (net (code "52") (name "unconnected-(POWER2-Pad4)") (class "Default")
      (node (ref "POWER2") (pin "4") (pinfunction "4_4") (pintype "unspecified"))
    )
    (net (code "53") (name "unconnected-(POWER_SW-Pad1)") (class "Default")
      (node (ref "POWER_SW") (pin "1") (pinfunction "1_1") (pintype "unspecified"))
    )
    (net (code "54") (name "unconnected-(POWER_SW-Pad4)") (class "Default")
      (node (ref "POWER_SW") (pin "4") (pinfunction "4_4") (pintype "unspecified"))
    )
    (net (code "55") (name "unconnected-(POWER_SW-Pad5)") (class "Default")
      (node (ref "POWER_SW") (pin "5") (pinfunction "5_5") (pintype "unspecified"))
    )
    (net (code "56") (name "unconnected-(R14-Pad3)") (class "Default")
      (node (ref "R14") (pin "3") (pinfunction "3_3") (pintype "unspecified"))
    )
    (net (code "57") (name "unconnected-(SCREW1-Pad1)") (class "Default")
      (node (ref "SCREW1") (pin "1") (pinfunction "1_1") (pintype "input"))
    )
    (net (code "58") (name "unconnected-(SCREW2-Pad1)") (class "Default")
      (node (ref "SCREW2") (pin "1") (pinfunction "1_1") (pintype "input"))
    )
    (net (code "59") (name "unconnected-(SCREW3-Pad1)") (class "Default")
      (node (ref "SCREW3") (pin "1") (pinfunction "1_1") (pintype "input"))
    )
    (net (code "60") (name "unconnected-(SCREW4-Pad1)") (class "Default")
      (node (ref "SCREW4") (pin "1") (pinfunction "1_1") (pintype "input"))
    )
    (net (code "61") (name "unconnected-(U1-EN-Pad3)") (class "Default")
      (node (ref "U1") (pin "3") (pinfunction "EN_3") (pintype "unspecified+no_connect"))
    )
    (net (code "62") (name "unconnected-(U14-EN-Pad3)") (class "Default")
      (node (ref "U14") (pin "3") (pinfunction "EN_3") (pintype "unspecified+no_connect"))
    )
    (net (code "63") (name "unconnected-(U15-EN-Pad3)") (class "Default")
      (node (ref "U15") (pin "3") (pinfunction "EN_3") (pintype "unspecified+no_connect"))
    )
    (net (code "64") (name "unconnected-(USB1-D+-Pad3)") (class "Default")
      (node (ref "USB1") (pin "3") (pinfunction "D+_3") (pintype "unspecified+no_connect"))
    )
    (net (code "65") (name "unconnected-(USB1-D--Pad2)") (class "Default")
      (node (ref "USB1") (pin "2") (pinfunction "D-_2") (pintype "unspecified+no_connect"))
    )
    (net (code "66") (name "unconnected-(USB_POWER-Pad1)") (class "Default")
      (node (ref "USB_POWER") (pin "1") (pinfunction "1_1") (pintype "unspecified"))
    )
    (net (code "67") (name "unconnected-(USB_POWER-Pad4)") (class "Default")
      (node (ref "USB_POWER") (pin "4") (pinfunction "4_4") (pintype "unspecified"))
    )
    (net (code "68") (name "unconnected-(USB_POWER-Pad5)") (class "Default")
      (node (ref "USB_POWER") (pin "5") (pinfunction "5_5") (pintype "unspecified"))
    )
    (net (code "69") (name "unconnected-(USER_POWER-Pad1)") (class "Default")
      (node (ref "USER_POWER") (pin "1") (pinfunction "1_1") (pintype "unspecified"))
    )
    (net (code "70") (name "unconnected-(USER_POWER-Pad4)") (class "Default")
      (node (ref "USER_POWER") (pin "4") (pinfunction "4_4") (pintype "unspecified"))
    )
    (net (code "71") (name "unconnected-(USER_POWER-Pad5)") (class "Default")
      (node (ref "USER_POWER") (pin "5") (pinfunction "5_5") (pintype "unspecified"))
    )
  )
)
